# analogBoardV1.net
KiCad netlist of a schematic drawn in EAGLE
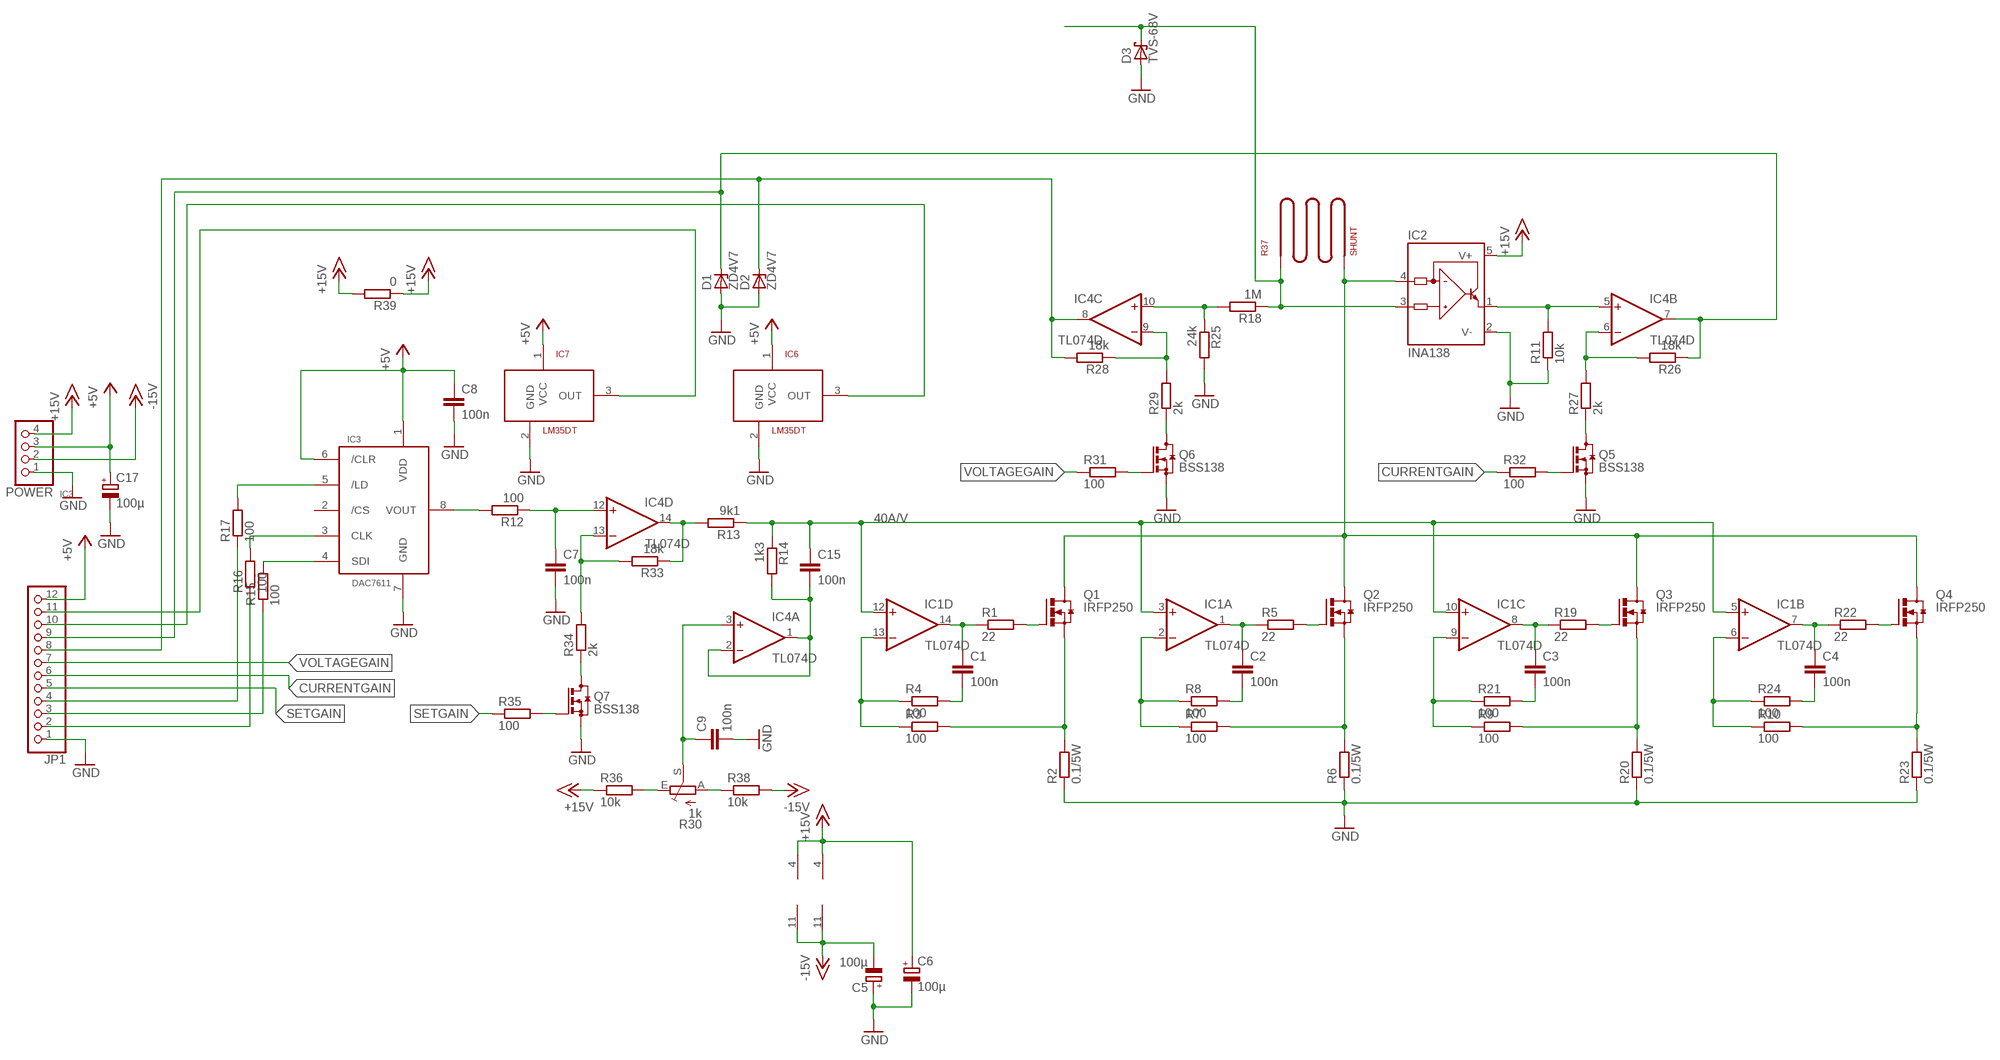
[diagram p0: schematic, sheet 1]

(export (version "E")
  (design (tool "Eeschema 10.0.6"))
  (components
    (comp (ref "C1")
      (value "100n")
      (footprint "eagle-import:C0603K")
      (libsource (lib "eagle-import") (part "C-EUC0603K"))
    )
    (comp (ref "C2")
      (value "100n")
      (footprint "eagle-import:C0603K")
      (libsource (lib "eagle-import") (part "C-EUC0603K"))
    )
    (comp (ref "C3")
      (value "100n")
      (footprint "eagle-import:C0603K")
      (libsource (lib "eagle-import") (part "C-EUC0603K"))
    )
    (comp (ref "C4")
      (value "100n")
      (footprint "eagle-import:C0603K")
      (libsource (lib "eagle-import") (part "C-EUC0603K"))
    )
    (comp (ref "C5")
      (value "100µ")
      (footprint "eagle-import:E2,5-6")
      (libsource (lib "eagle-import") (part "CPOL-EUE2.5-6"))
    )
    (comp (ref "C6")
      (value "100µ")
      (footprint "eagle-import:E2,5-6")
      (libsource (lib "eagle-import") (part "CPOL-EUE2.5-6"))
    )
    (comp (ref "C7")
      (value "100n")
      (footprint "eagle-import:C0603K")
      (libsource (lib "eagle-import") (part "C-EUC0603K"))
    )
    (comp (ref "C8")
      (value "100n")
      (footprint "eagle-import:C0603K")
      (libsource (lib "eagle-import") (part "C-EUC0603K"))
    )
    (comp (ref "C9")
      (value "100n")
      (footprint "eagle-import:C0603K")
      (libsource (lib "eagle-import") (part "C-EUC0603K"))
    )
    (comp (ref "C15")
      (value "100n")
      (footprint "eagle-import:C0603K")
      (libsource (lib "eagle-import") (part "C-EUC0603K"))
    )
    (comp (ref "C17")
      (value "100µ")
      (footprint "eagle-import:E2,5-6")
      (libsource (lib "eagle-import") (part "CPOL-EUE2.5-6"))
    )
    (comp (ref "D1")
      (value "ZD4V7")
      (footprint "eagle-import:SOT23")
      (libsource (lib "eagle-import") (part "ZENER-DIODESOT23"))
    )
    (comp (ref "D2")
      (value "ZD4V7")
      (footprint "eagle-import:SOT23")
      (libsource (lib "eagle-import") (part "ZENER-DIODESOT23"))
    )
    (comp (ref "D3")
      (value "TVS-68V")
      (footprint "eagle-import:CB429-15")
      (libsource (lib "eagle-import") (part "SCHOTTKY-DIODECB429-15"))
    )
    (comp (ref "IC1")
      (value "TL074D")
      (footprint "eagle-import:SO14")
      (libsource (lib "eagle-import") (part "TL074D"))
    )
    (comp (ref "IC2")
      (value "INA138")
      (footprint "eagle-import:SOT23-5")
      (fields (field (name "MF") "TEXAS INSTRUMENTS") (field (name "MPN") "INA138NA/250"))
      (libsource (lib "eagle-import") (part "INA138"))
    )
    (comp (ref "IC3")
      (value "DAC7611")
      (footprint "eagle-import:SO8")
      (libsource (lib "eagle-import") (part "DAC7611"))
    )
    (comp (ref "IC4")
      (value "TL074D")
      (footprint "eagle-import:SO14")
      (libsource (lib "eagle-import") (part "TL074D"))
    )
    (comp (ref "IC6")
      (value "LM35DT")
      (footprint "eagle-import:TO220V")
      (libsource (lib "eagle-import") (part "LM35DT"))
    )
    (comp (ref "IC7")
      (value "LM35DT")
      (footprint "eagle-import:TO220V")
      (libsource (lib "eagle-import") (part "LM35DT"))
    )
    (comp (ref "JP1")
      (value "PINHD-1X12")
      (footprint "eagle-import:1X12")
      (libsource (lib "eagle-import") (part "PINHD-1X12"))
    )
    (comp (ref "POWER")
      (value "PINHD-1X4")
      (footprint "eagle-import:1X04")
      (libsource (lib "eagle-import") (part "PINHD-1X4"))
    )
    (comp (ref "Q1")
      (value "IRFP250")
      (footprint "eagle-import:TO-247AD-V")
      (libsource (lib "eagle-import") (part "IRFP250"))
    )
    (comp (ref "Q2")
      (value "IRFP250")
      (footprint "eagle-import:TO-247AD-V")
      (libsource (lib "eagle-import") (part "IRFP250"))
    )
    (comp (ref "Q3")
      (value "IRFP250")
      (footprint "eagle-import:TO-247AD-V")
      (libsource (lib "eagle-import") (part "IRFP250"))
    )
    (comp (ref "Q4")
      (value "IRFP250")
      (footprint "eagle-import:TO-247AD-V")
      (libsource (lib "eagle-import") (part "IRFP250"))
    )
    (comp (ref "Q5")
      (value "BSS138")
      (footprint "eagle-import:SOT23")
      (libsource (lib "eagle-import") (part "BSS123"))
    )
    (comp (ref "Q6")
      (value "BSS138")
      (footprint "eagle-import:SOT23")
      (libsource (lib "eagle-import") (part "BSS123"))
    )
    (comp (ref "Q7")
      (value "BSS138")
      (footprint "eagle-import:SOT23")
      (libsource (lib "eagle-import") (part "BSS123"))
    )
    (comp (ref "R1")
      (value "22")
      (footprint "eagle-import:R0603")
      (libsource (lib "eagle-import") (part "R-EU_R0603"))
    )
    (comp (ref "R2")
      (value "0.1/5W")
      (footprint "eagle-import:5WAXIAL")
      (libsource (lib "eagle-import") (part "5WAXIAL"))
    )
    (comp (ref "R3")
      (value "100")
      (footprint "eagle-import:R0603")
      (libsource (lib "eagle-import") (part "R-EU_R0603"))
    )
    (comp (ref "R4")
      (value "100")
      (footprint "eagle-import:R0603")
      (libsource (lib "eagle-import") (part "R-EU_R0603"))
    )
    (comp (ref "R5")
      (value "22")
      (footprint "eagle-import:R0603")
      (libsource (lib "eagle-import") (part "R-EU_R0603"))
    )
    (comp (ref "R6")
      (value "0.1/5W")
      (footprint "eagle-import:5WAXIAL")
      (libsource (lib "eagle-import") (part "5WAXIAL"))
    )
    (comp (ref "R7")
      (value "100")
      (footprint "eagle-import:R0603")
      (libsource (lib "eagle-import") (part "R-EU_R0603"))
    )
    (comp (ref "R8")
      (value "100")
      (footprint "eagle-import:R0603")
      (libsource (lib "eagle-import") (part "R-EU_R0603"))
    )
    (comp (ref "R9")
      (value "100")
      (footprint "eagle-import:R0603")
      (libsource (lib "eagle-import") (part "R-EU_R0603"))
    )
    (comp (ref "R10")
      (value "100")
      (footprint "eagle-import:R0603")
      (libsource (lib "eagle-import") (part "R-EU_R0603"))
    )
    (comp (ref "R11")
      (value "10k")
      (footprint "eagle-import:R0603")
      (libsource (lib "eagle-import") (part "R-EU_R0603"))
    )
    (comp (ref "R12")
      (value "100")
      (footprint "eagle-import:R0603")
      (libsource (lib "eagle-import") (part "R-EU_R0603"))
    )
    (comp (ref "R13")
      (value "9k1")
      (footprint "eagle-import:R0603")
      (libsource (lib "eagle-import") (part "R-EU_R0603"))
    )
    (comp (ref "R14")
      (value "1k3")
      (footprint "eagle-import:R0603")
      (libsource (lib "eagle-import") (part "R-EU_R0603"))
    )
    (comp (ref "R15")
      (value "100")
      (footprint "eagle-import:R0603")
      (libsource (lib "eagle-import") (part "R-EU_R0603"))
    )
    (comp (ref "R16")
      (value "100")
      (footprint "eagle-import:R0603")
      (libsource (lib "eagle-import") (part "R-EU_R0603"))
    )
    (comp (ref "R17")
      (value "100")
      (footprint "eagle-import:R0603")
      (libsource (lib "eagle-import") (part "R-EU_R0603"))
    )
    (comp (ref "R18")
      (value "1M")
      (footprint "eagle-import:R0603")
      (libsource (lib "eagle-import") (part "R-EU_R0603"))
    )
    (comp (ref "R19")
      (value "22")
      (footprint "eagle-import:R0603")
      (libsource (lib "eagle-import") (part "R-EU_R0603"))
    )
    (comp (ref "R20")
      (value "0.1/5W")
      (footprint "eagle-import:5WAXIAL")
      (libsource (lib "eagle-import") (part "5WAXIAL"))
    )
    (comp (ref "R21")
      (value "100")
      (footprint "eagle-import:R0603")
      (libsource (lib "eagle-import") (part "R-EU_R0603"))
    )
    (comp (ref "R22")
      (value "22")
      (footprint "eagle-import:R0603")
      (libsource (lib "eagle-import") (part "R-EU_R0603"))
    )
    (comp (ref "R23")
      (value "0.1/5W")
      (footprint "eagle-import:5WAXIAL")
      (libsource (lib "eagle-import") (part "5WAXIAL"))
    )
    (comp (ref "R24")
      (value "100")
      (footprint "eagle-import:R0603")
      (libsource (lib "eagle-import") (part "R-EU_R0603"))
    )
    (comp (ref "R25")
      (value "24k")
      (footprint "eagle-import:R0603")
      (libsource (lib "eagle-import") (part "R-EU_R0603"))
    )
    (comp (ref "R26")
      (value "18k")
      (footprint "eagle-import:R0603")
      (libsource (lib "eagle-import") (part "R-EU_R0603"))
    )
    (comp (ref "R27")
      (value "2k")
      (footprint "eagle-import:R0603")
      (libsource (lib "eagle-import") (part "R-EU_R0603"))
    )
    (comp (ref "R28")
      (value "18k")
      (footprint "eagle-import:R0603")
      (libsource (lib "eagle-import") (part "R-EU_R0603"))
    )
    (comp (ref "R29")
      (value "2k")
      (footprint "eagle-import:R0603")
      (libsource (lib "eagle-import") (part "R-EU_R0603"))
    )
    (comp (ref "R30")
      (value "1k")
      (footprint "eagle-import:RJ9W")
      (libsource (lib "eagle-import") (part "TRIM_EU-RJ9W"))
    )
    (comp (ref "R31")
      (value "100")
      (footprint "eagle-import:R0603")
      (libsource (lib "eagle-import") (part "R-EU_R0603"))
    )
    (comp (ref "R32")
      (value "100")
      (footprint "eagle-import:R0603")
      (libsource (lib "eagle-import") (part "R-EU_R0603"))
    )
    (comp (ref "R33")
      (value "18k")
      (footprint "eagle-import:R0603")
      (libsource (lib "eagle-import") (part "R-EU_R0603"))
    )
    (comp (ref "R34")
      (value "2k")
      (footprint "eagle-import:R0603")
      (libsource (lib "eagle-import") (part "R-EU_R0603"))
    )
    (comp (ref "R35")
      (value "100")
      (footprint "eagle-import:R0603")
      (libsource (lib "eagle-import") (part "R-EU_R0603"))
    )
    (comp (ref "R36")
      (value "10k")
      (footprint "eagle-import:R0603")
      (libsource (lib "eagle-import") (part "R-EU_R0603"))
    )
    (comp (ref "R37")
      (value "SHUNT")
      (footprint "eagle-import:COPPERSHUNT")
      (libsource (lib "eagle-import") (part "SHUNT"))
    )
    (comp (ref "R38")
      (value "10k")
      (footprint "eagle-import:R0603")
      (libsource (lib "eagle-import") (part "R-EU_R0603"))
    )
    (comp (ref "R39")
      (value "0")
      (footprint "eagle-import:R1206")
      (libsource (lib "eagle-import") (part "R-EU_R1206"))
    )
  )
  (nets
    (net (code "1") (name "+5V") (class "Default")
      (node (ref "C17") (pin "+") (pinfunction "+_+") (pintype "passive"))
      (node (ref "C8") (pin "1") (pinfunction "1_1") (pintype "passive"))
      (node (ref "IC3") (pin "1") (pinfunction "VDD_1") (pintype "bidirectional"))
      (node (ref "IC3") (pin "6") (pinfunction "/CLR_6") (pintype "bidirectional"))
      (node (ref "IC6") (pin "1") (pinfunction "VCC_1") (pintype "bidirectional"))
      (node (ref "IC7") (pin "1") (pinfunction "VCC_1") (pintype "bidirectional"))
      (node (ref "JP1") (pin "12") (pinfunction "12_12") (pintype "passive"))
      (node (ref "POWER") (pin "3") (pinfunction "3_3") (pintype "passive"))
    )
    (net (code "2") (name "+15V") (class "Default")
      (node (ref "C6") (pin "+") (pinfunction "+_+") (pintype "passive"))
      (node (ref "IC1") (pin "4") (pinfunction "V+_4") (pintype "power_in"))
      (node (ref "IC2") (pin "5") (pinfunction "V+_5") (pintype "power_in"))
      (node (ref "IC4") (pin "4") (pinfunction "V+_4") (pintype "power_in"))
      (node (ref "POWER") (pin "4") (pinfunction "4_4") (pintype "passive"))
      (node (ref "R36") (pin "1") (pinfunction "1_1") (pintype "passive"))
      (node (ref "R39") (pin "1") (pinfunction "1_1") (pintype "passive"))
      (node (ref "R39") (pin "2") (pinfunction "2_2") (pintype "passive"))
    )
    (net (code "3") (name "-15V") (class "Default")
      (node (ref "C5") (pin "-") (pinfunction "-_-") (pintype "passive"))
      (node (ref "IC1") (pin "11") (pinfunction "V-_11") (pintype "power_in"))
      (node (ref "IC4") (pin "11") (pinfunction "V-_11") (pintype "power_in"))
      (node (ref "POWER") (pin "2") (pinfunction "2_2") (pintype "passive"))
      (node (ref "R38") (pin "2") (pinfunction "2_2") (pintype "passive"))
    )
    (net (code "4") (name "CURRENTGAIN") (class "Default")
      (node (ref "JP1") (pin "6") (pinfunction "6_6") (pintype "passive"))
      (node (ref "R32") (pin "1") (pinfunction "1_1") (pintype "passive"))
    )
    (net (code "5") (name "GND") (class "Default")
      (node (ref "C17") (pin "-") (pinfunction "-_-") (pintype "passive"))
      (node (ref "C5") (pin "+") (pinfunction "+_+") (pintype "passive"))
      (node (ref "C6") (pin "-") (pinfunction "-_-") (pintype "passive"))
      (node (ref "C7") (pin "2") (pinfunction "2_2") (pintype "passive"))
      (node (ref "C8") (pin "2") (pinfunction "2_2") (pintype "passive"))
      (node (ref "C9") (pin "2") (pinfunction "2_2") (pintype "passive"))
      (node (ref "D1") (pin "1") (pinfunction "A_1") (pintype "passive"))
      (node (ref "D2") (pin "1") (pinfunction "A_1") (pintype "passive"))
      (node (ref "D3") (pin "A") (pinfunction "A_A") (pintype "passive"))
      (node (ref "IC2") (pin "2") (pinfunction "V-_2") (pintype "power_in"))
      (node (ref "IC3") (pin "7") (pinfunction "GND_7") (pintype "bidirectional"))
      (node (ref "IC6") (pin "2") (pinfunction "GND_2") (pintype "bidirectional"))
      (node (ref "IC7") (pin "2") (pinfunction "GND_2") (pintype "bidirectional"))
      (node (ref "JP1") (pin "1") (pinfunction "1_1") (pintype "passive"))
      (node (ref "POWER") (pin "1") (pinfunction "1_1") (pintype "passive"))
      (node (ref "Q5") (pin "2") (pinfunction "S_2") (pintype "passive"))
      (node (ref "Q6") (pin "2") (pinfunction "S_2") (pintype "passive"))
      (node (ref "Q7") (pin "2") (pinfunction "S_2") (pintype "passive"))
      (node (ref "R11") (pin "1") (pinfunction "1_1") (pintype "passive"))
      (node (ref "R2") (pin "1") (pinfunction "1_1") (pintype "passive"))
      (node (ref "R20") (pin "1") (pinfunction "1_1") (pintype "passive"))
      (node (ref "R23") (pin "1") (pinfunction "1_1") (pintype "passive"))
      (node (ref "R25") (pin "2") (pinfunction "2_2") (pintype "passive"))
      (node (ref "R6") (pin "1") (pinfunction "1_1") (pintype "passive"))
    )
    (net (code "6") (name "Net-(C1-Pad2)") (class "Default")
      (node (ref "C1") (pin "2") (pinfunction "2_2") (pintype "passive"))
      (node (ref "R4") (pin "2") (pinfunction "2_2") (pintype "passive"))
    )
    (net (code "7") (name "Net-(C2-Pad2)") (class "Default")
      (node (ref "C2") (pin "2") (pinfunction "2_2") (pintype "passive"))
      (node (ref "R8") (pin "2") (pinfunction "2_2") (pintype "passive"))
    )
    (net (code "8") (name "Net-(C3-Pad2)") (class "Default")
      (node (ref "C3") (pin "2") (pinfunction "2_2") (pintype "passive"))
      (node (ref "R21") (pin "2") (pinfunction "2_2") (pintype "passive"))
    )
    (net (code "9") (name "Net-(C4-Pad2)") (class "Default")
      (node (ref "C4") (pin "2") (pinfunction "2_2") (pintype "passive"))
      (node (ref "R24") (pin "2") (pinfunction "2_2") (pintype "passive"))
    )
    (net (code "10") (name "Net-(D1-C)") (class "Default")
      (node (ref "D1") (pin "3") (pinfunction "C_3") (pintype "passive"))
      (node (ref "IC4") (pin "7") (pinfunction "OUT_7") (pintype "output"))
      (node (ref "JP1") (pin "9") (pinfunction "9_9") (pintype "passive"))
      (node (ref "R26") (pin "1") (pinfunction "1_1") (pintype "passive"))
    )
    (net (code "11") (name "Net-(D2-C)") (class "Default")
      (node (ref "D2") (pin "3") (pinfunction "C_3") (pintype "passive"))
      (node (ref "IC4") (pin "8") (pinfunction "OUT_8") (pintype "output"))
      (node (ref "JP1") (pin "8") (pinfunction "8_8") (pintype "passive"))
      (node (ref "R28") (pin "2") (pinfunction "2_2") (pintype "passive"))
    )
    (net (code "12") (name "Net-(IC1A-+IN)") (class "Default")
      (node (ref "C15") (pin "1") (pinfunction "1_1") (pintype "passive"))
      (node (ref "IC1") (pin "10") (pinfunction "+IN_10") (pintype "input"))
      (node (ref "IC1") (pin "12") (pinfunction "+IN_12") (pintype "input"))
      (node (ref "IC1") (pin "3") (pinfunction "+IN_3") (pintype "input"))
      (node (ref "IC1") (pin "5") (pinfunction "+IN_5") (pintype "input"))
      (node (ref "R13") (pin "1") (pinfunction "1_1") (pintype "passive"))
      (node (ref "R14") (pin "1") (pinfunction "1_1") (pintype "passive"))
    )
    (net (code "13") (name "Net-(IC1A--IN)") (class "Default")
      (node (ref "IC1") (pin "2") (pinfunction "-IN_2") (pintype "input"))
      (node (ref "R7") (pin "1") (pinfunction "1_1") (pintype "passive"))
      (node (ref "R8") (pin "1") (pinfunction "1_1") (pintype "passive"))
    )
    (net (code "14") (name "Net-(IC1A-OUT)") (class "Default")
      (node (ref "C2") (pin "1") (pinfunction "1_1") (pintype "passive"))
      (node (ref "IC1") (pin "1") (pinfunction "OUT_1") (pintype "output"))
      (node (ref "R5") (pin "1") (pinfunction "1_1") (pintype "passive"))
    )
    (net (code "15") (name "Net-(IC1B--IN)") (class "Default")
      (node (ref "IC1") (pin "6") (pinfunction "-IN_6") (pintype "input"))
      (node (ref "R10") (pin "1") (pinfunction "1_1") (pintype "passive"))
      (node (ref "R24") (pin "1") (pinfunction "1_1") (pintype "passive"))
    )
    (net (code "16") (name "Net-(IC1B-OUT)") (class "Default")
      (node (ref "C4") (pin "1") (pinfunction "1_1") (pintype "passive"))
      (node (ref "IC1") (pin "7") (pinfunction "OUT_7") (pintype "output"))
      (node (ref "R22") (pin "1") (pinfunction "1_1") (pintype "passive"))
    )
    (net (code "17") (name "Net-(IC1C--IN)") (class "Default")
      (node (ref "IC1") (pin "9") (pinfunction "-IN_9") (pintype "input"))
      (node (ref "R21") (pin "1") (pinfunction "1_1") (pintype "passive"))
      (node (ref "R9") (pin "1") (pinfunction "1_1") (pintype "passive"))
    )
    (net (code "18") (name "Net-(IC1C-OUT)") (class "Default")
      (node (ref "C3") (pin "1") (pinfunction "1_1") (pintype "passive"))
      (node (ref "IC1") (pin "8") (pinfunction "OUT_8") (pintype "output"))
      (node (ref "R19") (pin "1") (pinfunction "1_1") (pintype "passive"))
    )
    (net (code "19") (name "Net-(IC1D--IN)") (class "Default")
      (node (ref "IC1") (pin "13") (pinfunction "-IN_13") (pintype "input"))
      (node (ref "R3") (pin "1") (pinfunction "1_1") (pintype "passive"))
      (node (ref "R4") (pin "1") (pinfunction "1_1") (pintype "passive"))
    )
    (net (code "20") (name "Net-(IC1D-OUT)") (class "Default")
      (node (ref "C1") (pin "1") (pinfunction "1_1") (pintype "passive"))
      (node (ref "IC1") (pin "14") (pinfunction "OUT_14") (pintype "output"))
      (node (ref "R1") (pin "1") (pinfunction "1_1") (pintype "passive"))
    )
    (net (code "21") (name "Net-(IC2-IN+)") (class "Default")
      (node (ref "D3") (pin "C") (pinfunction "C_C") (pintype "passive"))
      (node (ref "IC2") (pin "3") (pinfunction "IN+_3") (pintype "input"))
      (node (ref "R18") (pin "1") (pinfunction "1_1") (pintype "passive"))
      (node (ref "R37") (pin "P$1") (pinfunction "P$1_P$1") (pintype "bidirectional"))
    )
    (net (code "22") (name "Net-(IC2-IN-)") (class "Default")
      (node (ref "IC2") (pin "4") (pinfunction "IN-_4") (pintype "input"))
      (node (ref "Q1") (pin "D") (pinfunction "D_D") (pintype "passive"))
      (node (ref "Q2") (pin "D") (pinfunction "D_D") (pintype "passive"))
      (node (ref "Q3") (pin "D") (pinfunction "D_D") (pintype "passive"))
      (node (ref "Q4") (pin "D") (pinfunction "D_D") (pintype "passive"))
      (node (ref "R37") (pin "P$2") (pinfunction "P$2_P$2") (pintype "bidirectional"))
    )
    (net (code "23") (name "Net-(IC2-OUT)") (class "Default")
      (node (ref "IC2") (pin "1") (pinfunction "OUT_1") (pintype "output"))
      (node (ref "IC4") (pin "5") (pinfunction "+IN_5") (pintype "input"))
      (node (ref "R11") (pin "2") (pinfunction "2_2") (pintype "passive"))
    )
    (net (code "24") (name "Net-(IC3-CLK)") (class "Default")
      (node (ref "IC3") (pin "3") (pinfunction "CLK_3") (pintype "bidirectional"))
      (node (ref "R16") (pin "2") (pinfunction "2_2") (pintype "passive"))
    )
    (net (code "25") (name "Net-(IC3-SDI)") (class "Default")
      (node (ref "IC3") (pin "4") (pinfunction "SDI_4") (pintype "bidirectional"))
      (node (ref "R15") (pin "2") (pinfunction "2_2") (pintype "passive"))
    )
    (net (code "26") (name "Net-(IC3-VOUT)") (class "Default")
      (node (ref "IC3") (pin "8") (pinfunction "VOUT_8") (pintype "bidirectional"))
      (node (ref "R12") (pin "2") (pinfunction "2_2") (pintype "passive"))
    )
    (net (code "27") (name "Net-(IC3-{slash}LD)") (class "Default")
      (node (ref "IC3") (pin "5") (pinfunction "/LD_5") (pintype "bidirectional"))
      (node (ref "R17") (pin "2") (pinfunction "2_2") (pintype "passive"))
    )
    (net (code "28") (name "Net-(IC4A-+IN)") (class "Default")
      (node (ref "C9") (pin "1") (pinfunction "1_1") (pintype "passive"))
      (node (ref "IC4") (pin "3") (pinfunction "+IN_3") (pintype "input"))
      (node (ref "R30") (pin "S") (pinfunction "S_S") (pintype "passive"))
    )
    (net (code "29") (name "Net-(IC4A--IN)") (class "Default")
      (node (ref "C15") (pin "2") (pinfunction "2_2") (pintype "passive"))
      (node (ref "IC4") (pin "1") (pinfunction "OUT_1") (pintype "output"))
      (node (ref "IC4") (pin "2") (pinfunction "-IN_2") (pintype "input"))
      (node (ref "R14") (pin "2") (pinfunction "2_2") (pintype "passive"))
    )
    (net (code "30") (name "Net-(IC4B--IN)") (class "Default")
      (node (ref "IC4") (pin "6") (pinfunction "-IN_6") (pintype "input"))
      (node (ref "R26") (pin "2") (pinfunction "2_2") (pintype "passive"))
      (node (ref "R27") (pin "2") (pinfunction "2_2") (pintype "passive"))
    )
    (net (code "31") (name "Net-(IC4C-+IN)") (class "Default")
      (node (ref "IC4") (pin "10") (pinfunction "+IN_10") (pintype "input"))
      (node (ref "R18") (pin "2") (pinfunction "2_2") (pintype "passive"))
      (node (ref "R25") (pin "1") (pinfunction "1_1") (pintype "passive"))
    )
    (net (code "32") (name "Net-(IC4C--IN)") (class "Default")
      (node (ref "IC4") (pin "9") (pinfunction "-IN_9") (pintype "input"))
      (node (ref "R28") (pin "1") (pinfunction "1_1") (pintype "passive"))
      (node (ref "R29") (pin "2") (pinfunction "2_2") (pintype "passive"))
    )
    (net (code "33") (name "Net-(IC4D-+IN)") (class "Default")
      (node (ref "C7") (pin "1") (pinfunction "1_1") (pintype "passive"))
      (node (ref "IC4") (pin "12") (pinfunction "+IN_12") (pintype "input"))
      (node (ref "R12") (pin "1") (pinfunction "1_1") (pintype "passive"))
    )
    (net (code "34") (name "Net-(IC4D--IN)") (class "Default")
      (node (ref "IC4") (pin "13") (pinfunction "-IN_13") (pintype "input"))
      (node (ref "R33") (pin "2") (pinfunction "2_2") (pintype "passive"))
      (node (ref "R34") (pin "2") (pinfunction "2_2") (pintype "passive"))
    )
    (net (code "35") (name "Net-(IC4D-OUT)") (class "Default")
      (node (ref "IC4") (pin "14") (pinfunction "OUT_14") (pintype "output"))
      (node (ref "R13") (pin "2") (pinfunction "2_2") (pintype "passive"))
      (node (ref "R33") (pin "1") (pinfunction "1_1") (pintype "passive"))
    )
    (net (code "36") (name "Net-(IC6-OUT)") (class "Default")
      (node (ref "IC6") (pin "3") (pinfunction "OUT_3") (pintype "bidirectional"))
      (node (ref "JP1") (pin "10") (pinfunction "10_10") (pintype "passive"))
    )
    (net (code "37") (name "Net-(IC7-OUT)") (class "Default")
      (node (ref "IC7") (pin "3") (pinfunction "OUT_3") (pintype "bidirectional"))
      (node (ref "JP1") (pin "11") (pinfunction "11_11") (pintype "passive"))
    )
    (net (code "38") (name "Net-(JP1-Pad2)") (class "Default")
      (node (ref "JP1") (pin "2") (pinfunction "2_2") (pintype "passive"))
      (node (ref "R16") (pin "1") (pinfunction "1_1") (pintype "passive"))
    )
    (net (code "39") (name "Net-(JP1-Pad3)") (class "Default")
      (node (ref "JP1") (pin "3") (pinfunction "3_3") (pintype "passive"))
      (node (ref "R15") (pin "1") (pinfunction "1_1") (pintype "passive"))
    )
    (net (code "40") (name "Net-(JP1-Pad4)") (class "Default")
      (node (ref "JP1") (pin "4") (pinfunction "4_4") (pintype "passive"))
      (node (ref "R17") (pin "1") (pinfunction "1_1") (pintype "passive"))
    )
    (net (code "41") (name "Net-(Q1-PadG)") (class "Default")
      (node (ref "Q1") (pin "G") (pinfunction "G_G") (pintype "passive"))
      (node (ref "R1") (pin "2") (pinfunction "2_2") (pintype "passive"))
    )
    (net (code "42") (name "Net-(Q1-PadS)") (class "Default")
      (node (ref "Q1") (pin "S") (pinfunction "S_S") (pintype "passive"))
      (node (ref "R2") (pin "2") (pinfunction "2_2") (pintype "passive"))
      (node (ref "R3") (pin "2") (pinfunction "2_2") (pintype "passive"))
    )
    (net (code "43") (name "Net-(Q2-PadG)") (class "Default")
      (node (ref "Q2") (pin "G") (pinfunction "G_G") (pintype "passive"))
      (node (ref "R5") (pin "2") (pinfunction "2_2") (pintype "passive"))
    )
    (net (code "44") (name "Net-(Q2-PadS)") (class "Default")
      (node (ref "Q2") (pin "S") (pinfunction "S_S") (pintype "passive"))
      (node (ref "R6") (pin "2") (pinfunction "2_2") (pintype "passive"))
      (node (ref "R7") (pin "2") (pinfunction "2_2") (pintype "passive"))
    )
    (net (code "45") (name "Net-(Q3-PadG)") (class "Default")
      (node (ref "Q3") (pin "G") (pinfunction "G_G") (pintype "passive"))
      (node (ref "R19") (pin "2") (pinfunction "2_2") (pintype "passive"))
    )
    (net (code "46") (name "Net-(Q3-PadS)") (class "Default")
      (node (ref "Q3") (pin "S") (pinfunction "S_S") (pintype "passive"))
      (node (ref "R20") (pin "2") (pinfunction "2_2") (pintype "passive"))
      (node (ref "R9") (pin "2") (pinfunction "2_2") (pintype "passive"))
    )
    (net (code "47") (name "Net-(Q4-PadG)") (class "Default")
      (node (ref "Q4") (pin "G") (pinfunction "G_G") (pintype "passive"))
      (node (ref "R22") (pin "2") (pinfunction "2_2") (pintype "passive"))
    )
    (net (code "48") (name "Net-(Q4-PadS)") (class "Default")
      (node (ref "Q4") (pin "S") (pinfunction "S_S") (pintype "passive"))
      (node (ref "R10") (pin "2") (pinfunction "2_2") (pintype "passive"))
      (node (ref "R23") (pin "2") (pinfunction "2_2") (pintype "passive"))
    )
    (net (code "49") (name "Net-(Q5-D)") (class "Default")
      (node (ref "Q5") (pin "3") (pinfunction "D_3") (pintype "passive"))
      (node (ref "R27") (pin "1") (pinfunction "1_1") (pintype "passive"))
    )
    (net (code "50") (name "Net-(Q5-G)") (class "Default")
      (node (ref "Q5") (pin "1") (pinfunction "G_1") (pintype "passive"))
      (node (ref "R32") (pin "2") (pinfunction "2_2") (pintype "passive"))
    )
    (net (code "51") (name "Net-(Q6-D)") (class "Default")
      (node (ref "Q6") (pin "3") (pinfunction "D_3") (pintype "passive"))
      (node (ref "R29") (pin "1") (pinfunction "1_1") (pintype "passive"))
    )
    (net (code "52") (name "Net-(Q6-G)") (class "Default")
      (node (ref "Q6") (pin "1") (pinfunction "G_1") (pintype "passive"))
      (node (ref "R31") (pin "2") (pinfunction "2_2") (pintype "passive"))
    )
    (net (code "53") (name "Net-(Q7-D)") (class "Default")
      (node (ref "Q7") (pin "3") (pinfunction "D_3") (pintype "passive"))
      (node (ref "R34") (pin "1") (pinfunction "1_1") (pintype "passive"))
    )
    (net (code "54") (name "Net-(Q7-G)") (class "Default")
      (node (ref "Q7") (pin "1") (pinfunction "G_1") (pintype "passive"))
      (node (ref "R35") (pin "2") (pinfunction "2_2") (pintype "passive"))
    )
    (net (code "55") (name "Net-(R30-PadA)") (class "Default")
      (node (ref "R30") (pin "A") (pinfunction "A_A") (pintype "passive"))
      (node (ref "R38") (pin "1") (pinfunction "1_1") (pintype "passive"))
    )
    (net (code "56") (name "Net-(R30-PadE)") (class "Default")
      (node (ref "R30") (pin "E") (pinfunction "E_E") (pintype "passive"))
      (node (ref "R36") (pin "2") (pinfunction "2_2") (pintype "passive"))
    )
    (net (code "57") (name "SETGAIN") (class "Default")
      (node (ref "JP1") (pin "5") (pinfunction "5_5") (pintype "passive"))
      (node (ref "R35") (pin "1") (pinfunction "1_1") (pintype "passive"))
    )
    (net (code "58") (name "VOLTAGEGAIN") (class "Default")
      (node (ref "JP1") (pin "7") (pinfunction "7_7") (pintype "passive"))
      (node (ref "R31") (pin "1") (pinfunction "1_1") (pintype "passive"))
    )
    (net (code "59") (name "unconnected-(IC3-{slash}CS-Pad2)") (class "Default")
      (node (ref "IC3") (pin "2") (pinfunction "/CS_2") (pintype "bidirectional"))
    )
  )
)
